# untitled_B.net
KiCad netlist of a schematic drawn in EAGLE
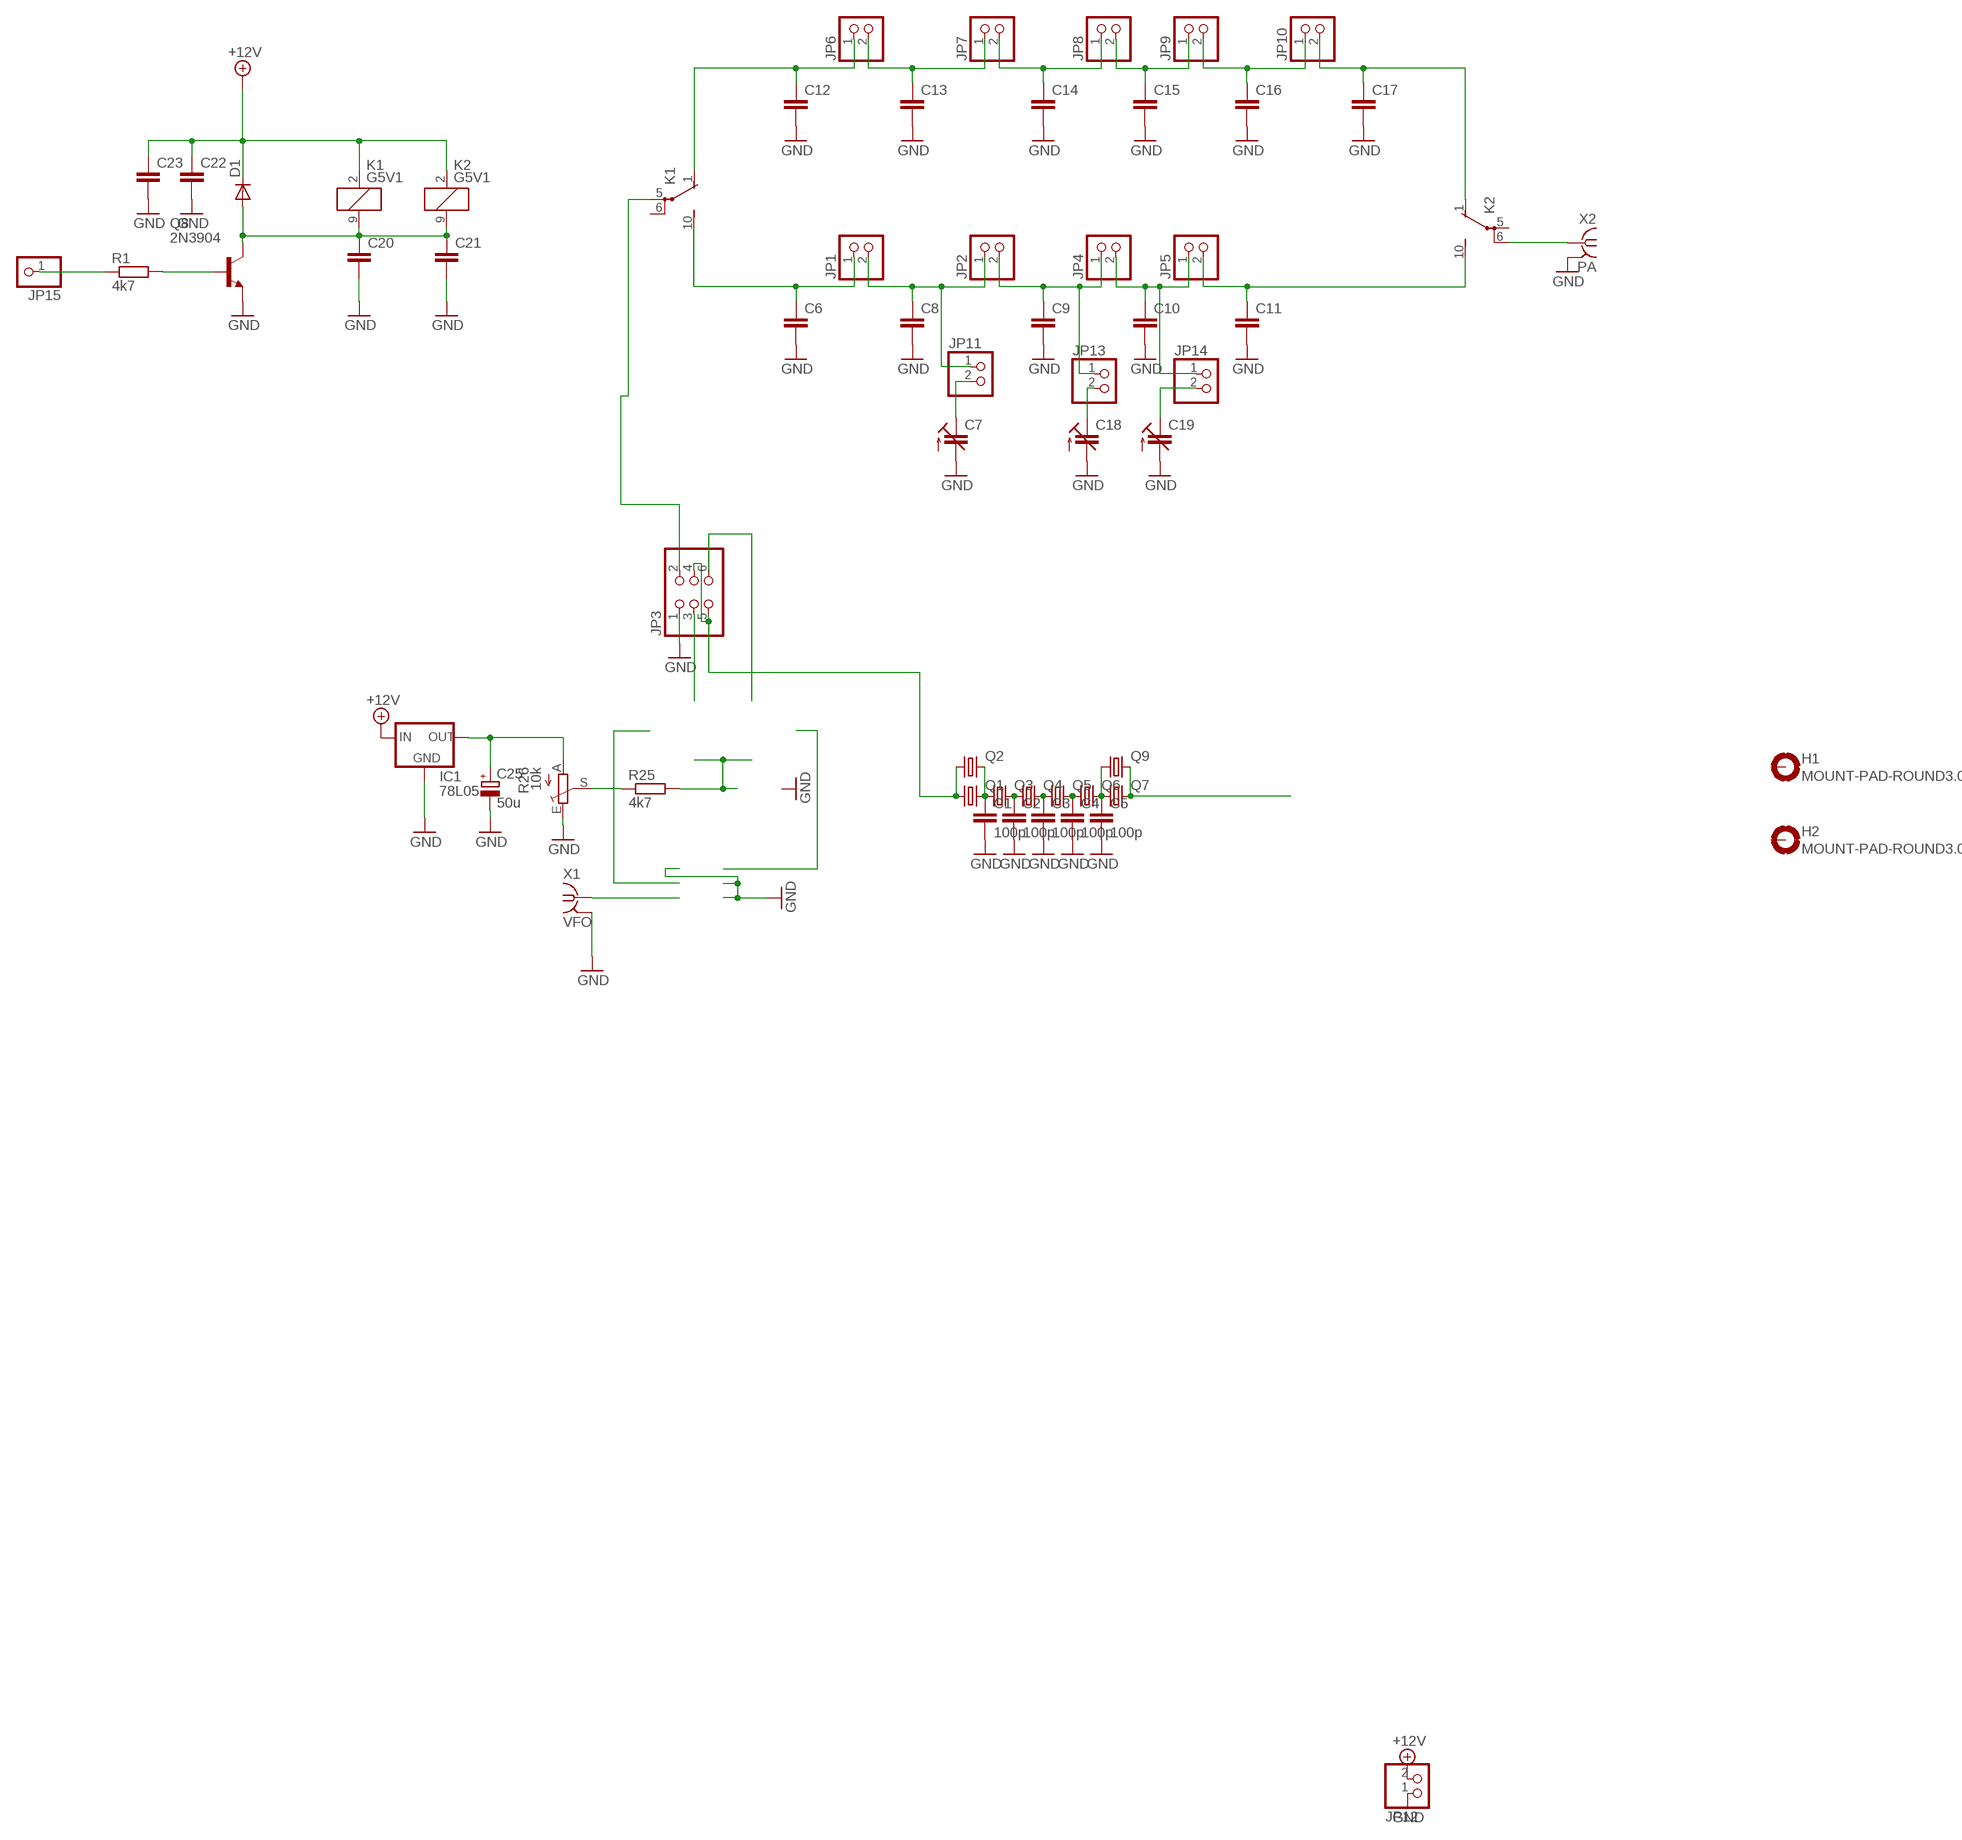
[diagram p0: schematic, sheet 1]

(export (version "E")
  (design (tool "Eeschema 10.0.6"))
  (components
    (comp (ref "C1")
      (value "100p")
      (footprint "eagle-import:C1206")
      (libsource (lib "eagle-import") (part "C-EUC1206"))
    )
    (comp (ref "C2")
      (value "100p")
      (footprint "eagle-import:C1206")
      (libsource (lib "eagle-import") (part "C-EUC1206"))
    )
    (comp (ref "C3")
      (value "100p")
      (footprint "eagle-import:C1206")
      (libsource (lib "eagle-import") (part "C-EUC1206"))
    )
    (comp (ref "C4")
      (value "100p")
      (footprint "eagle-import:C1206")
      (libsource (lib "eagle-import") (part "C-EUC1206"))
    )
    (comp (ref "C5")
      (value "100p")
      (footprint "eagle-import:C1206")
      (libsource (lib "eagle-import") (part "C-EUC1206"))
    )
    (comp (ref "C6")
      (value "C-EU050-024X044")
      (footprint "eagle-import:C050-024X044")
      (libsource (lib "eagle-import") (part "C-EU050-024X044"))
    )
    (comp (ref "C7")
      (value "C-TRIMMTZ03")
      (footprint "eagle-import:CTRIMTZ03")
      (libsource (lib "eagle-import") (part "C-TRIMMTZ03"))
    )
    (comp (ref "C8")
      (value "C-EU050-024X044")
      (footprint "eagle-import:C050-024X044")
      (libsource (lib "eagle-import") (part "C-EU050-024X044"))
    )
    (comp (ref "C9")
      (value "C-EU050-024X044")
      (footprint "eagle-import:C050-024X044")
      (libsource (lib "eagle-import") (part "C-EU050-024X044"))
    )
    (comp (ref "C10")
      (value "C-EU050-024X044")
      (footprint "eagle-import:C050-024X044")
      (libsource (lib "eagle-import") (part "C-EU050-024X044"))
    )
    (comp (ref "C11")
      (value "C-EU050-024X044")
      (footprint "eagle-import:C050-024X044")
      (libsource (lib "eagle-import") (part "C-EU050-024X044"))
    )
    (comp (ref "C12")
      (value "C-EU050-024X044")
      (footprint "eagle-import:C050-024X044")
      (libsource (lib "eagle-import") (part "C-EU050-024X044"))
    )
    (comp (ref "C13")
      (value "C-EU050-024X044")
      (footprint "eagle-import:C050-024X044")
      (libsource (lib "eagle-import") (part "C-EU050-024X044"))
    )
    (comp (ref "C14")
      (value "C-EU050-024X044")
      (footprint "eagle-import:C050-024X044")
      (libsource (lib "eagle-import") (part "C-EU050-024X044"))
    )
    (comp (ref "C15")
      (value "C-EU050-024X044")
      (footprint "eagle-import:C050-024X044")
      (libsource (lib "eagle-import") (part "C-EU050-024X044"))
    )
    (comp (ref "C16")
      (value "C-EU050-024X044")
      (footprint "eagle-import:C050-024X044")
      (libsource (lib "eagle-import") (part "C-EU050-024X044"))
    )
    (comp (ref "C17")
      (value "C-EU050-024X044")
      (footprint "eagle-import:C050-024X044")
      (libsource (lib "eagle-import") (part "C-EU050-024X044"))
    )
    (comp (ref "C18")
      (value "C-TRIMMTZ03")
      (footprint "eagle-import:CTRIMTZ03")
      (libsource (lib "eagle-import") (part "C-TRIMMTZ03"))
    )
    (comp (ref "C19")
      (value "C-TRIMMTZ03")
      (footprint "eagle-import:CTRIMTZ03")
      (libsource (lib "eagle-import") (part "C-TRIMMTZ03"))
    )
    (comp (ref "C20")
      (value "C-EU050-024X044")
      (footprint "eagle-import:C050-024X044")
      (libsource (lib "eagle-import") (part "C-EU050-024X044"))
    )
    (comp (ref "C21")
      (value "C-EU050-024X044")
      (footprint "eagle-import:C050-024X044")
      (libsource (lib "eagle-import") (part "C-EU050-024X044"))
    )
    (comp (ref "C22")
      (value "C-EU050-024X044")
      (footprint "eagle-import:C050-024X044")
      (libsource (lib "eagle-import") (part "C-EU050-024X044"))
    )
    (comp (ref "C23")
      (value "C-EU050-024X044")
      (footprint "eagle-import:C050-024X044")
      (libsource (lib "eagle-import") (part "C-EU050-024X044"))
    )
    (comp (ref "C25")
      (value "50u")
      (footprint "eagle-import:E2,5-5")
      (libsource (lib "eagle-import") (part "CPOL-EUE2.5-5"))
    )
    (comp (ref "D1")
      (value "DIODE-D-5")
      (footprint "eagle-import:D-5")
      (libsource (lib "eagle-import") (part "DIODE-D-5"))
    )
    (comp (ref "H1")
      (value "MOUNT-PAD-ROUND3.0")
      (footprint "eagle-import:3,0-PAD")
      (libsource (lib "eagle-import") (part "MOUNT-PAD-ROUND3.0"))
    )
    (comp (ref "H2")
      (value "MOUNT-PAD-ROUND3.0")
      (footprint "eagle-import:3,0-PAD")
      (libsource (lib "eagle-import") (part "MOUNT-PAD-ROUND3.0"))
    )
    (comp (ref "IC1")
      (value "78L05")
      (footprint "eagle-import:78LXX")
      (libsource (lib "eagle-import") (part "78LXX"))
    )
    (comp (ref "JP1")
      (value "PINHD-1X2")
      (footprint "eagle-import:1X02")
      (libsource (lib "eagle-import") (part "PINHD-1X2"))
    )
    (comp (ref "JP2")
      (value "PINHD-1X2")
      (footprint "eagle-import:1X02")
      (libsource (lib "eagle-import") (part "PINHD-1X2"))
    )
    (comp (ref "JP3")
      (value "PINHD-2X3")
      (footprint "eagle-import:2X03")
      (libsource (lib "eagle-import") (part "PINHD-2X3"))
    )
    (comp (ref "JP4")
      (value "PINHD-1X2")
      (footprint "eagle-import:1X02")
      (libsource (lib "eagle-import") (part "PINHD-1X2"))
    )
    (comp (ref "JP5")
      (value "PINHD-1X2")
      (footprint "eagle-import:1X02")
      (libsource (lib "eagle-import") (part "PINHD-1X2"))
    )
    (comp (ref "JP6")
      (value "PINHD-1X2")
      (footprint "eagle-import:1X02")
      (libsource (lib "eagle-import") (part "PINHD-1X2"))
    )
    (comp (ref "JP7")
      (value "PINHD-1X2")
      (footprint "eagle-import:1X02")
      (libsource (lib "eagle-import") (part "PINHD-1X2"))
    )
    (comp (ref "JP8")
      (value "PINHD-1X2")
      (footprint "eagle-import:1X02")
      (libsource (lib "eagle-import") (part "PINHD-1X2"))
    )
    (comp (ref "JP9")
      (value "PINHD-1X2")
      (footprint "eagle-import:1X02")
      (libsource (lib "eagle-import") (part "PINHD-1X2"))
    )
    (comp (ref "JP10")
      (value "PINHD-1X2")
      (footprint "eagle-import:1X02")
      (libsource (lib "eagle-import") (part "PINHD-1X2"))
    )
    (comp (ref "JP11")
      (value "PINHD-1X2")
      (footprint "eagle-import:1X02")
      (libsource (lib "eagle-import") (part "PINHD-1X2"))
    )
    (comp (ref "JP12")
      (value "PINHD-1X2")
      (footprint "eagle-import:1X02")
      (libsource (lib "eagle-import") (part "PINHD-1X2"))
    )
    (comp (ref "JP13")
      (value "PINHD-1X2")
      (footprint "eagle-import:1X02")
      (libsource (lib "eagle-import") (part "PINHD-1X2"))
    )
    (comp (ref "JP14")
      (value "PINHD-1X2")
      (footprint "eagle-import:1X02")
      (libsource (lib "eagle-import") (part "PINHD-1X2"))
    )
    (comp (ref "JP15")
      (value "PINHD-1X1")
      (footprint "eagle-import:1X01")
      (libsource (lib "eagle-import") (part "PINHD-1X1"))
    )
    (comp (ref "K1")
      (value "G5V1")
      (footprint "eagle-import:G5V1")
      (fields (field (name "MPN") "G5V-1-DC24"))
      (libsource (lib "eagle-import") (part "G5V1"))
    )
    (comp (ref "K2")
      (value "G5V1")
      (footprint "eagle-import:G5V1")
      (fields (field (name "MPN") "G5V-1-DC24"))
      (libsource (lib "eagle-import") (part "G5V1"))
    )
    (comp (ref "Q1")
      (value "CRYSTALHC49S")
      (footprint "eagle-import:HC49_S")
      (libsource (lib "eagle-import") (part "CRYSTALHC49S"))
    )
    (comp (ref "Q2")
      (value "CRYSTALHC49S")
      (footprint "eagle-import:HC49_S")
      (libsource (lib "eagle-import") (part "CRYSTALHC49S"))
    )
    (comp (ref "Q3")
      (value "CRYSTALHC49S")
      (footprint "eagle-import:HC49_S")
      (libsource (lib "eagle-import") (part "CRYSTALHC49S"))
    )
    (comp (ref "Q4")
      (value "CRYSTALHC49S")
      (footprint "eagle-import:HC49_S")
      (libsource (lib "eagle-import") (part "CRYSTALHC49S"))
    )
    (comp (ref "Q5")
      (value "CRYSTALHC49S")
      (footprint "eagle-import:HC49_S")
      (libsource (lib "eagle-import") (part "CRYSTALHC49S"))
    )
    (comp (ref "Q6")
      (value "CRYSTALHC49S")
      (footprint "eagle-import:HC49_S")
      (libsource (lib "eagle-import") (part "CRYSTALHC49S"))
    )
    (comp (ref "Q7")
      (value "CRYSTALHC49S")
      (footprint "eagle-import:HC49_S")
      (libsource (lib "eagle-import") (part "CRYSTALHC49S"))
    )
    (comp (ref "Q8")
      (value "2N3904")
      (footprint "eagle-import:TO92")
      (libsource (lib "eagle-import") (part "2N3904"))
    )
    (comp (ref "Q9")
      (value "CRYSTALHC49S")
      (footprint "eagle-import:HC49_S")
      (libsource (lib "eagle-import") (part "CRYSTALHC49S"))
    )
    (comp (ref "R1")
      (value "4k7")
      (footprint "eagle-import:0204_5")
      (libsource (lib "eagle-import") (part "R-EU_0204/5"))
    )
    (comp (ref "R25")
      (value "4k7")
      (footprint "eagle-import:0204_5")
      (libsource (lib "eagle-import") (part "R-EU_0204/5"))
    )
    (comp (ref "R26")
      (value "10k")
      (footprint "eagle-import:CA6V")
      (libsource (lib "eagle-import") (part "TRIM_EU-CA6V"))
    )
    (comp (ref "X1")
      (value "VFO")
      (footprint "eagle-import:BU-SMA-V")
      (libsource (lib "eagle-import") (part "BU-SMA-V"))
    )
    (comp (ref "X2")
      (value "PA")
      (footprint "eagle-import:BU-SMA-V")
      (fields (field (name "OC_FARNELL") "unknown") (field (name "OC_NEWARK") "unknown"))
      (libsource (lib "eagle-import") (part "BU-SMA-V"))
    )
  )
  (nets
    (net (code "1") (name "+12V") (class "Default")
      (node (ref "C22") (pin "1") (pinfunction "1_1") (pintype "passive"))
      (node (ref "C23") (pin "1") (pinfunction "1_1") (pintype "passive"))
      (node (ref "D1") (pin "C") (pinfunction "C_C") (pintype "passive"))
      (node (ref "IC1") (pin "IN") (pinfunction "IN_IN") (pintype "input"))
      (node (ref "JP12") (pin "2") (pinfunction "2_2") (pintype "passive"))
      (node (ref "K1") (pin "2") (pinfunction "1_2") (pintype "passive"))
      (node (ref "K2") (pin "2") (pinfunction "1_2") (pintype "passive"))
    )
    (net (code "2") (name "GND") (class "Default")
      (node (ref "C1") (pin "2") (pinfunction "2_2") (pintype "passive"))
      (node (ref "C10") (pin "2") (pinfunction "2_2") (pintype "passive"))
      (node (ref "C11") (pin "2") (pinfunction "2_2") (pintype "passive"))
      (node (ref "C12") (pin "2") (pinfunction "2_2") (pintype "passive"))
      (node (ref "C13") (pin "2") (pinfunction "2_2") (pintype "passive"))
      (node (ref "C14") (pin "2") (pinfunction "2_2") (pintype "passive"))
      (node (ref "C15") (pin "2") (pinfunction "2_2") (pintype "passive"))
      (node (ref "C16") (pin "2") (pinfunction "2_2") (pintype "passive"))
      (node (ref "C17") (pin "2") (pinfunction "2_2") (pintype "passive"))
      (node (ref "C18") (pin "2") (pinfunction "A_2") (pintype "passive"))
      (node (ref "C19") (pin "2") (pinfunction "A_2") (pintype "passive"))
      (node (ref "C2") (pin "2") (pinfunction "2_2") (pintype "passive"))
      (node (ref "C20") (pin "2") (pinfunction "2_2") (pintype "passive"))
      (node (ref "C21") (pin "2") (pinfunction "2_2") (pintype "passive"))
      (node (ref "C22") (pin "2") (pinfunction "2_2") (pintype "passive"))
      (node (ref "C23") (pin "2") (pinfunction "2_2") (pintype "passive"))
      (node (ref "C25") (pin "-") (pinfunction "-_-") (pintype "passive"))
      (node (ref "C3") (pin "2") (pinfunction "2_2") (pintype "passive"))
      (node (ref "C4") (pin "2") (pinfunction "2_2") (pintype "passive"))
      (node (ref "C5") (pin "2") (pinfunction "2_2") (pintype "passive"))
      (node (ref "C6") (pin "2") (pinfunction "2_2") (pintype "passive"))
      (node (ref "C7") (pin "2") (pinfunction "A_2") (pintype "passive"))
      (node (ref "C8") (pin "2") (pinfunction "2_2") (pintype "passive"))
      (node (ref "C9") (pin "2") (pinfunction "2_2") (pintype "passive"))
      (node (ref "IC1") (pin "GND") (pinfunction "GND_GND") (pintype "input"))
      (node (ref "JP12") (pin "1") (pinfunction "1_1") (pintype "passive"))
      (node (ref "JP3") (pin "1") (pinfunction "1_1") (pintype "passive"))
      (node (ref "Q8") (pin "3") (pinfunction "E_3") (pintype "passive"))
      (node (ref "R26") (pin "E") (pinfunction "E_E") (pintype "passive"))
      (node (ref "X1") (pin "2") (pinfunction "GND_2") (pintype "power_in"))
      (node (ref "X2") (pin "2") (pinfunction "GND_2") (pintype "power_in"))
    )
    (net (code "3") (name "Net-(C1-Pad1)") (class "Default")
      (node (ref "C1") (pin "1") (pinfunction "1_1") (pintype "passive"))
      (node (ref "Q1") (pin "2") (pinfunction "2_2") (pintype "passive"))
      (node (ref "Q2") (pin "2") (pinfunction "2_2") (pintype "passive"))
      (node (ref "Q3") (pin "1") (pinfunction "1_1") (pintype "passive"))
    )
    (net (code "4") (name "Net-(C2-Pad1)") (class "Default")
      (node (ref "C2") (pin "1") (pinfunction "1_1") (pintype "passive"))
      (node (ref "Q3") (pin "2") (pinfunction "2_2") (pintype "passive"))
      (node (ref "Q4") (pin "1") (pinfunction "1_1") (pintype "passive"))
    )
    (net (code "5") (name "Net-(C3-Pad1)") (class "Default")
      (node (ref "C3") (pin "1") (pinfunction "1_1") (pintype "passive"))
      (node (ref "Q4") (pin "2") (pinfunction "2_2") (pintype "passive"))
      (node (ref "Q5") (pin "1") (pinfunction "1_1") (pintype "passive"))
    )
    (net (code "6") (name "Net-(C4-Pad1)") (class "Default")
      (node (ref "C4") (pin "1") (pinfunction "1_1") (pintype "passive"))
      (node (ref "Q5") (pin "2") (pinfunction "2_2") (pintype "passive"))
      (node (ref "Q6") (pin "1") (pinfunction "1_1") (pintype "passive"))
    )
    (net (code "7") (name "Net-(C5-Pad1)") (class "Default")
      (node (ref "C5") (pin "1") (pinfunction "1_1") (pintype "passive"))
      (node (ref "Q6") (pin "2") (pinfunction "2_2") (pintype "passive"))
      (node (ref "Q7") (pin "1") (pinfunction "1_1") (pintype "passive"))
      (node (ref "Q9") (pin "1") (pinfunction "1_1") (pintype "passive"))
    )
    (net (code "8") (name "Net-(C7-E)") (class "Default")
      (node (ref "C7") (pin "1") (pinfunction "E_1") (pintype "passive"))
      (node (ref "JP11") (pin "2") (pinfunction "2_2") (pintype "passive"))
    )
    (net (code "9") (name "Net-(C8-Pad1)") (class "Default")
      (node (ref "C8") (pin "1") (pinfunction "1_1") (pintype "passive"))
      (node (ref "JP1") (pin "2") (pinfunction "2_2") (pintype "passive"))
      (node (ref "JP11") (pin "1") (pinfunction "1_1") (pintype "passive"))
      (node (ref "JP2") (pin "1") (pinfunction "1_1") (pintype "passive"))
    )
    (net (code "10") (name "Net-(C9-Pad1)") (class "Default")
      (node (ref "C9") (pin "1") (pinfunction "1_1") (pintype "passive"))
      (node (ref "JP13") (pin "1") (pinfunction "1_1") (pintype "passive"))
      (node (ref "JP2") (pin "2") (pinfunction "2_2") (pintype "passive"))
      (node (ref "JP4") (pin "1") (pinfunction "1_1") (pintype "passive"))
    )
    (net (code "11") (name "Net-(C10-Pad1)") (class "Default")
      (node (ref "C10") (pin "1") (pinfunction "1_1") (pintype "passive"))
      (node (ref "JP14") (pin "1") (pinfunction "1_1") (pintype "passive"))
      (node (ref "JP4") (pin "2") (pinfunction "2_2") (pintype "passive"))
      (node (ref "JP5") (pin "1") (pinfunction "1_1") (pintype "passive"))
    )
    (net (code "12") (name "Net-(C13-Pad1)") (class "Default")
      (node (ref "C13") (pin "1") (pinfunction "1_1") (pintype "passive"))
      (node (ref "JP6") (pin "2") (pinfunction "2_2") (pintype "passive"))
      (node (ref "JP7") (pin "1") (pinfunction "1_1") (pintype "passive"))
    )
    (net (code "13") (name "Net-(C14-Pad1)") (class "Default")
      (node (ref "C14") (pin "1") (pinfunction "1_1") (pintype "passive"))
      (node (ref "JP7") (pin "2") (pinfunction "2_2") (pintype "passive"))
      (node (ref "JP8") (pin "1") (pinfunction "1_1") (pintype "passive"))
    )
    (net (code "14") (name "Net-(C15-Pad1)") (class "Default")
      (node (ref "C15") (pin "1") (pinfunction "1_1") (pintype "passive"))
      (node (ref "JP8") (pin "2") (pinfunction "2_2") (pintype "passive"))
      (node (ref "JP9") (pin "1") (pinfunction "1_1") (pintype "passive"))
    )
    (net (code "15") (name "Net-(C16-Pad1)") (class "Default")
      (node (ref "C16") (pin "1") (pinfunction "1_1") (pintype "passive"))
      (node (ref "JP10") (pin "1") (pinfunction "1_1") (pintype "passive"))
      (node (ref "JP9") (pin "2") (pinfunction "2_2") (pintype "passive"))
    )
    (net (code "16") (name "Net-(C18-E)") (class "Default")
      (node (ref "C18") (pin "1") (pinfunction "E_1") (pintype "passive"))
      (node (ref "JP13") (pin "2") (pinfunction "2_2") (pintype "passive"))
    )
    (net (code "17") (name "Net-(C19-E)") (class "Default")
      (node (ref "C19") (pin "1") (pinfunction "E_1") (pintype "passive"))
      (node (ref "JP14") (pin "2") (pinfunction "2_2") (pintype "passive"))
    )
    (net (code "18") (name "Net-(C25-Pad+)") (class "Default")
      (node (ref "C25") (pin "+") (pinfunction "+_+") (pintype "passive"))
      (node (ref "IC1") (pin "OUT") (pinfunction "OUT_OUT") (pintype "passive"))
      (node (ref "R26") (pin "A") (pinfunction "A_A") (pintype "passive"))
    )
    (net (code "19") (name "Net-(JP3-Pad2)") (class "Default")
      (node (ref "JP3") (pin "2") (pinfunction "2_2") (pintype "passive"))
      (node (ref "K1") (pin "5") (pinfunction "P_5") (pintype "passive"))
    )
    (net (code "20") (name "Net-(JP3-Pad4)") (class "Default")
      (node (ref "JP3") (pin "4") (pinfunction "4_4") (pintype "passive"))
      (node (ref "JP3") (pin "5") (pinfunction "5_5") (pintype "passive"))
      (node (ref "Q1") (pin "1") (pinfunction "1_1") (pintype "passive"))
      (node (ref "Q2") (pin "1") (pinfunction "1_1") (pintype "passive"))
    )
    (net (code "21") (name "Net-(JP15-Pad1)") (class "Default")
      (node (ref "JP15") (pin "1") (pinfunction "1_1") (pintype "passive"))
      (node (ref "R1") (pin "1") (pinfunction "1_1") (pintype "passive"))
    )
    (net (code "22") (name "Net-(K1A-2)") (class "Default")
      (node (ref "C20") (pin "1") (pinfunction "1_1") (pintype "passive"))
      (node (ref "C21") (pin "1") (pinfunction "1_1") (pintype "passive"))
      (node (ref "D1") (pin "A") (pinfunction "A_A") (pintype "passive"))
      (node (ref "K1") (pin "9") (pinfunction "2_9") (pintype "passive"))
      (node (ref "K2") (pin "9") (pinfunction "2_9") (pintype "passive"))
      (node (ref "Q8") (pin "1") (pinfunction "C_1") (pintype "passive"))
    )
    (net (code "23") (name "Net-(K1B-O)") (class "Default")
      (node (ref "C12") (pin "1") (pinfunction "1_1") (pintype "passive"))
      (node (ref "JP6") (pin "1") (pinfunction "1_1") (pintype "passive"))
      (node (ref "K1") (pin "1") (pinfunction "O_1") (pintype "passive"))
    )
    (net (code "24") (name "Net-(K1B-S)") (class "Default")
      (node (ref "C6") (pin "1") (pinfunction "1_1") (pintype "passive"))
      (node (ref "JP1") (pin "1") (pinfunction "1_1") (pintype "passive"))
      (node (ref "K1") (pin "10") (pinfunction "S_10") (pintype "passive"))
    )
    (net (code "25") (name "Net-(K2B-O)") (class "Default")
      (node (ref "C17") (pin "1") (pinfunction "1_1") (pintype "passive"))
      (node (ref "JP10") (pin "2") (pinfunction "2_2") (pintype "passive"))
      (node (ref "K2") (pin "1") (pinfunction "O_1") (pintype "passive"))
    )
    (net (code "26") (name "Net-(K2B-P-Pad6)") (class "Default")
      (node (ref "K2") (pin "6") (pinfunction "P_6") (pintype "passive"))
      (node (ref "X2") (pin "1") (pinfunction "1_1") (pintype "passive"))
    )
    (net (code "27") (name "Net-(K2B-S)") (class "Default")
      (node (ref "C11") (pin "1") (pinfunction "1_1") (pintype "passive"))
      (node (ref "JP5") (pin "2") (pinfunction "2_2") (pintype "passive"))
      (node (ref "K2") (pin "10") (pinfunction "S_10") (pintype "passive"))
    )
    (net (code "28") (name "Net-(Q7-Pad2)") (class "Default")
      (node (ref "Q7") (pin "2") (pinfunction "2_2") (pintype "passive"))
      (node (ref "Q9") (pin "2") (pinfunction "2_2") (pintype "passive"))
    )
    (net (code "29") (name "Net-(Q8-B)") (class "Default")
      (node (ref "Q8") (pin "2") (pinfunction "B_2") (pintype "passive"))
      (node (ref "R1") (pin "2") (pinfunction "2_2") (pintype "passive"))
    )
    (net (code "30") (name "Net-(R25-Pad1)") (class "Default")
      (node (ref "R25") (pin "1") (pinfunction "1_1") (pintype "passive"))
      (node (ref "R26") (pin "S") (pinfunction "S_S") (pintype "passive"))
    )
    (net (code "31") (name "unconnected-(H1-MOUNT-PadB3,0)") (class "Default")
      (node (ref "H1") (pin "B3,0") (pinfunction "MOUNT_B3,0") (pintype "passive"))
    )
    (net (code "32") (name "unconnected-(H2-MOUNT-PadB3,0)") (class "Default")
      (node (ref "H2") (pin "B3,0") (pinfunction "MOUNT_B3,0") (pintype "passive"))
    )
    (net (code "33") (name "unconnected-(JP3-Pad3)") (class "Default")
      (node (ref "JP3") (pin "3") (pinfunction "3_3") (pintype "passive"))
    )
    (net (code "34") (name "unconnected-(JP3-Pad6)") (class "Default")
      (node (ref "JP3") (pin "6") (pinfunction "6_6") (pintype "passive"))
    )
    (net (code "35") (name "unconnected-(K1B-P-Pad6)") (class "Default")
      (node (ref "K1") (pin "6") (pinfunction "P_6") (pintype "passive"))
    )
    (net (code "36") (name "unconnected-(K2B-P-Pad5)") (class "Default")
      (node (ref "K2") (pin "5") (pinfunction "P_5") (pintype "passive"))
    )
    (net (code "37") (name "unconnected-(R25-Pad2)") (class "Default")
      (node (ref "R25") (pin "2") (pinfunction "2_2") (pintype "passive"))
    )
    (net (code "38") (name "unconnected-(X1-Pad1)") (class "Default")
      (node (ref "X1") (pin "1") (pinfunction "1_1") (pintype "passive"))
    )
  )
)
